# BlinkyCircuit.net
KiCad netlist of a schematic drawn in EAGLE
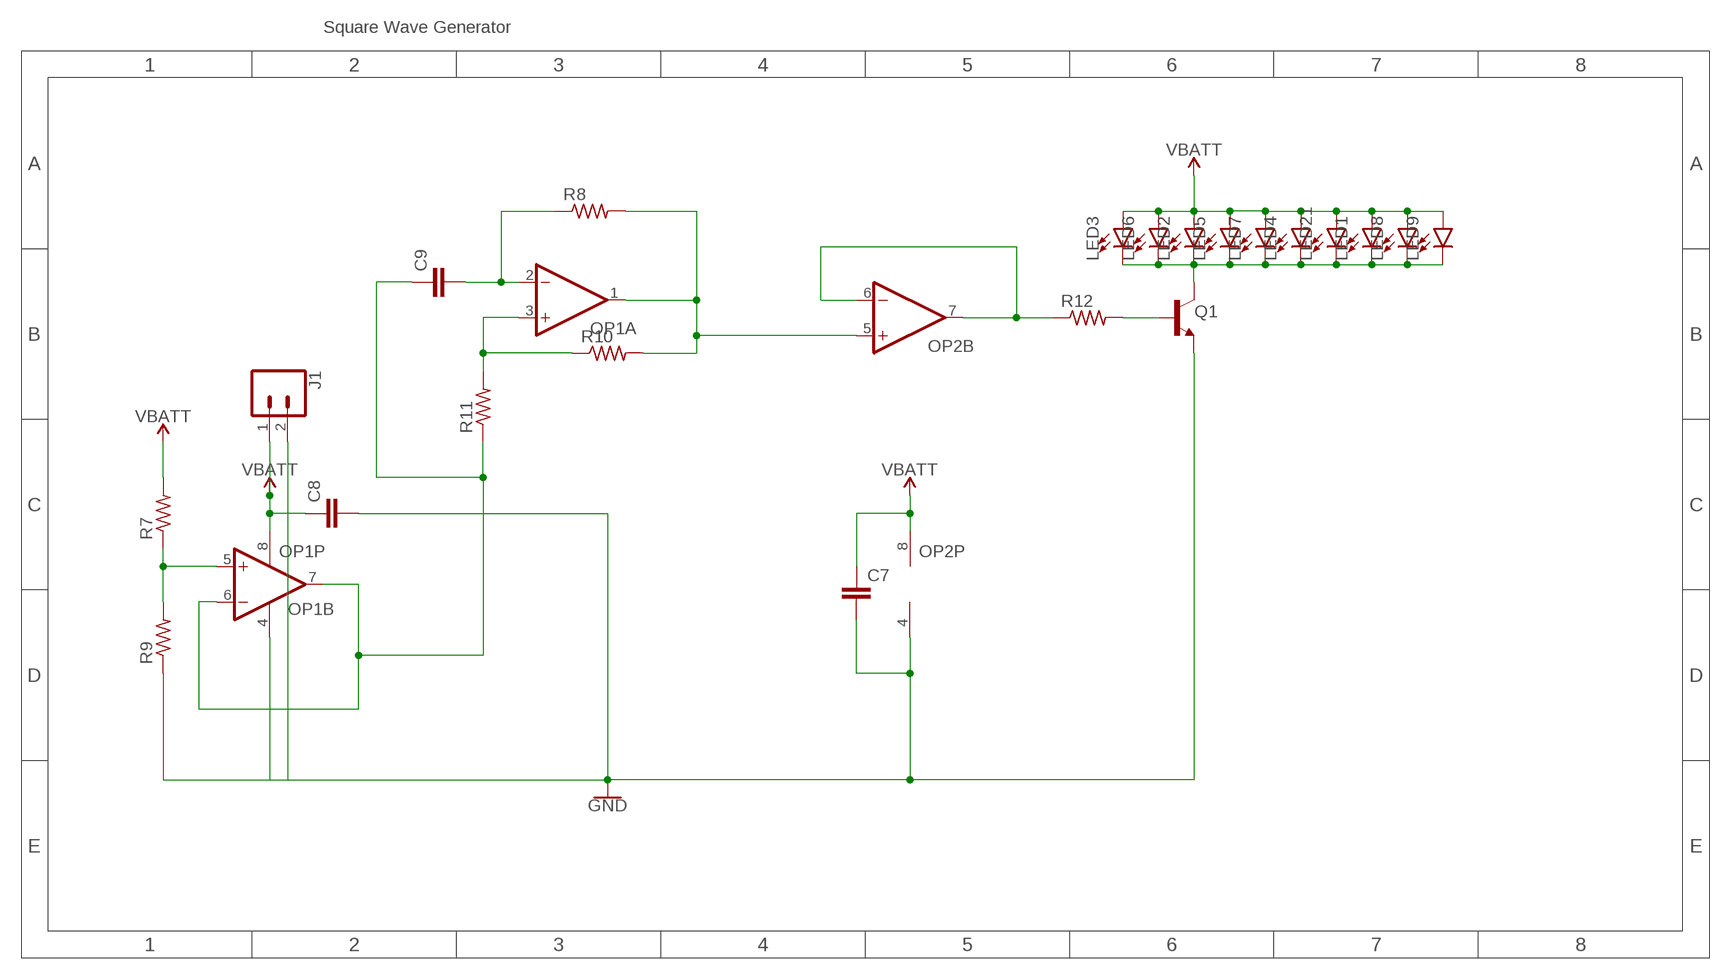
[diagram p0: schematic, sheet 1]

(export (version "E")
  (design (tool "Eeschema 10.0.6"))
  (components
    (comp (ref "C7")
      (value "CAPACITOR0603")
      (footprint "eagle-import:C0603")
      (libsource (lib "eagle-import") (part "CAPACITOR0603"))
    )
    (comp (ref "C8")
      (value "CAPACITOR0603")
      (footprint "eagle-import:C0603")
      (libsource (lib "eagle-import") (part "CAPACITOR0603"))
    )
    (comp (ref "C9")
      (value "CAPACITOR0603")
      (footprint "eagle-import:C0603")
      (libsource (lib "eagle-import") (part "CAPACITOR0603"))
    )
    (comp (ref "J1")
      (value "CONN_02")
      (footprint "eagle-import:1X02")
      (libsource (lib "eagle-import") (part "CONN_02"))
    )
    (comp (ref "LED1")
      (value "LED5MM")
      (footprint "eagle-import:LED_5MM")
      (libsource (lib "eagle-import") (part "LED5MM"))
    )
    (comp (ref "LED2")
      (value "LED5MM")
      (footprint "eagle-import:LED_5MM")
      (libsource (lib "eagle-import") (part "LED5MM"))
    )
    (comp (ref "LED3")
      (value "LED5MM")
      (footprint "eagle-import:LED_5MM")
      (libsource (lib "eagle-import") (part "LED5MM"))
    )
    (comp (ref "LED4")
      (value "LED5MM")
      (footprint "eagle-import:LED_5MM")
      (libsource (lib "eagle-import") (part "LED5MM"))
    )
    (comp (ref "LED5")
      (value "LED5MM")
      (footprint "eagle-import:LED_5MM")
      (libsource (lib "eagle-import") (part "LED5MM"))
    )
    (comp (ref "LED6")
      (value "LED5MM")
      (footprint "eagle-import:LED_5MM")
      (libsource (lib "eagle-import") (part "LED5MM"))
    )
    (comp (ref "LED7")
      (value "LED5MM")
      (footprint "eagle-import:LED_5MM")
      (libsource (lib "eagle-import") (part "LED5MM"))
    )
    (comp (ref "LED8")
      (value "LED5MM")
      (footprint "eagle-import:LED_5MM")
      (libsource (lib "eagle-import") (part "LED5MM"))
    )
    (comp (ref "LED9")
      (value "LED5MM")
      (footprint "eagle-import:LED_5MM")
      (libsource (lib "eagle-import") (part "LED5MM"))
    )
    (comp (ref "LED21")
      (value "LED5MM")
      (footprint "eagle-import:LED_5MM")
      (libsource (lib "eagle-import") (part "LED5MM"))
    )
    (comp (ref "OP1")
      (value "OP-DUALR")
      (footprint "eagle-import:SO8")
      (fields (field (name "MPN") "AD8607ARMZ-R2"))
      (libsource (lib "eagle-import") (part "OP-DUALR"))
    )
    (comp (ref "OP2")
      (value "OP-DUALR")
      (footprint "eagle-import:SO8")
      (fields (field (name "MPN") "AD8607ARMZ-R2"))
      (libsource (lib "eagle-import") (part "OP-DUALR"))
    )
    (comp (ref "Q1")
      (value "NPN-GENERIC")
      (footprint "eagle-import:SOT23-3")
      (libsource (lib "eagle-import") (part "NPN-GENERIC"))
    )
    (comp (ref "R7")
      (value "RESISTOR0603")
      (footprint "eagle-import:R0603")
      (libsource (lib "eagle-import") (part "RESISTOR0603"))
    )
    (comp (ref "R8")
      (value "RESISTOR0603")
      (footprint "eagle-import:R0603")
      (libsource (lib "eagle-import") (part "RESISTOR0603"))
    )
    (comp (ref "R9")
      (value "RESISTOR0603")
      (footprint "eagle-import:R0603")
      (libsource (lib "eagle-import") (part "RESISTOR0603"))
    )
    (comp (ref "R10")
      (value "RESISTOR0603")
      (footprint "eagle-import:R0603")
      (libsource (lib "eagle-import") (part "RESISTOR0603"))
    )
    (comp (ref "R11")
      (value "RESISTOR0603")
      (footprint "eagle-import:R0603")
      (libsource (lib "eagle-import") (part "RESISTOR0603"))
    )
    (comp (ref "R12")
      (value "RESISTOR0603")
      (footprint "eagle-import:R0603")
      (libsource (lib "eagle-import") (part "RESISTOR0603"))
    )
  )
  (nets
    (net (code "1") (name "GND") (class "Default")
      (node (ref "C7") (pin "2") (pinfunction "2_2") (pintype "passive"))
      (node (ref "C8") (pin "2") (pinfunction "2_2") (pintype "passive"))
      (node (ref "J1") (pin "2") (pinfunction "2_2") (pintype "passive"))
      (node (ref "OP1") (pin "4") (pinfunction "V-_4") (pintype "power_in"))
      (node (ref "OP2") (pin "4") (pinfunction "V-_4") (pintype "power_in"))
      (node (ref "Q1") (pin "2") (pinfunction "E_2") (pintype "passive"))
      (node (ref "R9") (pin "1") (pinfunction "1_1") (pintype "passive"))
    )
    (net (code "2") (name "Net-(LED1-C)") (class "Default")
      (node (ref "LED1") (pin "K") (pinfunction "C_K") (pintype "passive"))
      (node (ref "LED2") (pin "K") (pinfunction "C_K") (pintype "passive"))
      (node (ref "LED21") (pin "K") (pinfunction "C_K") (pintype "passive"))
      (node (ref "LED3") (pin "K") (pinfunction "C_K") (pintype "passive"))
      (node (ref "LED4") (pin "K") (pinfunction "C_K") (pintype "passive"))
      (node (ref "LED5") (pin "K") (pinfunction "C_K") (pintype "passive"))
      (node (ref "LED6") (pin "K") (pinfunction "C_K") (pintype "passive"))
      (node (ref "LED7") (pin "K") (pinfunction "C_K") (pintype "passive"))
      (node (ref "LED8") (pin "K") (pinfunction "C_K") (pintype "passive"))
      (node (ref "LED9") (pin "K") (pinfunction "C_K") (pintype "passive"))
      (node (ref "Q1") (pin "3") (pinfunction "C_3") (pintype "passive"))
    )
    (net (code "3") (name "Net-(OP1A-+IN)") (class "Default")
      (node (ref "OP1") (pin "3") (pinfunction "+IN_3") (pintype "input"))
      (node (ref "R10") (pin "1") (pinfunction "1_1") (pintype "passive"))
      (node (ref "R11") (pin "2") (pinfunction "2_2") (pintype "passive"))
    )
    (net (code "4") (name "Net-(OP1A--IN)") (class "Default")
      (node (ref "C9") (pin "2") (pinfunction "2_2") (pintype "passive"))
      (node (ref "OP1") (pin "2") (pinfunction "-IN_2") (pintype "input"))
      (node (ref "R8") (pin "1") (pinfunction "1_1") (pintype "passive"))
    )
    (net (code "5") (name "Net-(OP1A-OUT)") (class "Default")
      (node (ref "OP1") (pin "1") (pinfunction "OUT_1") (pintype "output"))
      (node (ref "OP2") (pin "5") (pinfunction "+IN_5") (pintype "input"))
      (node (ref "R10") (pin "2") (pinfunction "2_2") (pintype "passive"))
      (node (ref "R8") (pin "2") (pinfunction "2_2") (pintype "passive"))
    )
    (net (code "6") (name "Net-(OP1B-+IN)") (class "Default")
      (node (ref "OP1") (pin "5") (pinfunction "+IN_5") (pintype "input"))
      (node (ref "R7") (pin "1") (pinfunction "1_1") (pintype "passive"))
      (node (ref "R9") (pin "2") (pinfunction "2_2") (pintype "passive"))
    )
    (net (code "7") (name "Net-(OP1B--IN)") (class "Default")
      (node (ref "C9") (pin "1") (pinfunction "1_1") (pintype "passive"))
      (node (ref "OP1") (pin "6") (pinfunction "-IN_6") (pintype "input"))
      (node (ref "OP1") (pin "7") (pinfunction "OUT_7") (pintype "output"))
      (node (ref "R11") (pin "1") (pinfunction "1_1") (pintype "passive"))
    )
    (net (code "8") (name "Net-(OP2B--IN)") (class "Default")
      (node (ref "OP2") (pin "6") (pinfunction "-IN_6") (pintype "input"))
      (node (ref "OP2") (pin "7") (pinfunction "OUT_7") (pintype "output"))
      (node (ref "R12") (pin "1") (pinfunction "1_1") (pintype "passive"))
    )
    (net (code "9") (name "Net-(Q1-B)") (class "Default")
      (node (ref "Q1") (pin "1") (pinfunction "B_1") (pintype "passive"))
      (node (ref "R12") (pin "2") (pinfunction "2_2") (pintype "passive"))
    )
    (net (code "10") (name "VBATT") (class "Default")
      (node (ref "C7") (pin "1") (pinfunction "1_1") (pintype "passive"))
      (node (ref "C8") (pin "1") (pinfunction "1_1") (pintype "passive"))
      (node (ref "J1") (pin "1") (pinfunction "1_1") (pintype "passive"))
      (node (ref "LED1") (pin "A") (pinfunction "A_A") (pintype "passive"))
      (node (ref "LED2") (pin "A") (pinfunction "A_A") (pintype "passive"))
      (node (ref "LED21") (pin "A") (pinfunction "A_A") (pintype "passive"))
      (node (ref "LED3") (pin "A") (pinfunction "A_A") (pintype "passive"))
      (node (ref "LED4") (pin "A") (pinfunction "A_A") (pintype "passive"))
      (node (ref "LED5") (pin "A") (pinfunction "A_A") (pintype "passive"))
      (node (ref "LED6") (pin "A") (pinfunction "A_A") (pintype "passive"))
      (node (ref "LED7") (pin "A") (pinfunction "A_A") (pintype "passive"))
      (node (ref "LED8") (pin "A") (pinfunction "A_A") (pintype "passive"))
      (node (ref "LED9") (pin "A") (pinfunction "A_A") (pintype "passive"))
      (node (ref "OP1") (pin "8") (pinfunction "V+_8") (pintype "power_in"))
      (node (ref "OP2") (pin "8") (pinfunction "V+_8") (pintype "power_in"))
      (node (ref "R7") (pin "2") (pinfunction "2_2") (pintype "passive"))
    )
  )
)
